# Power.net
KiCad netlist of a schematic drawn in Altium Designer
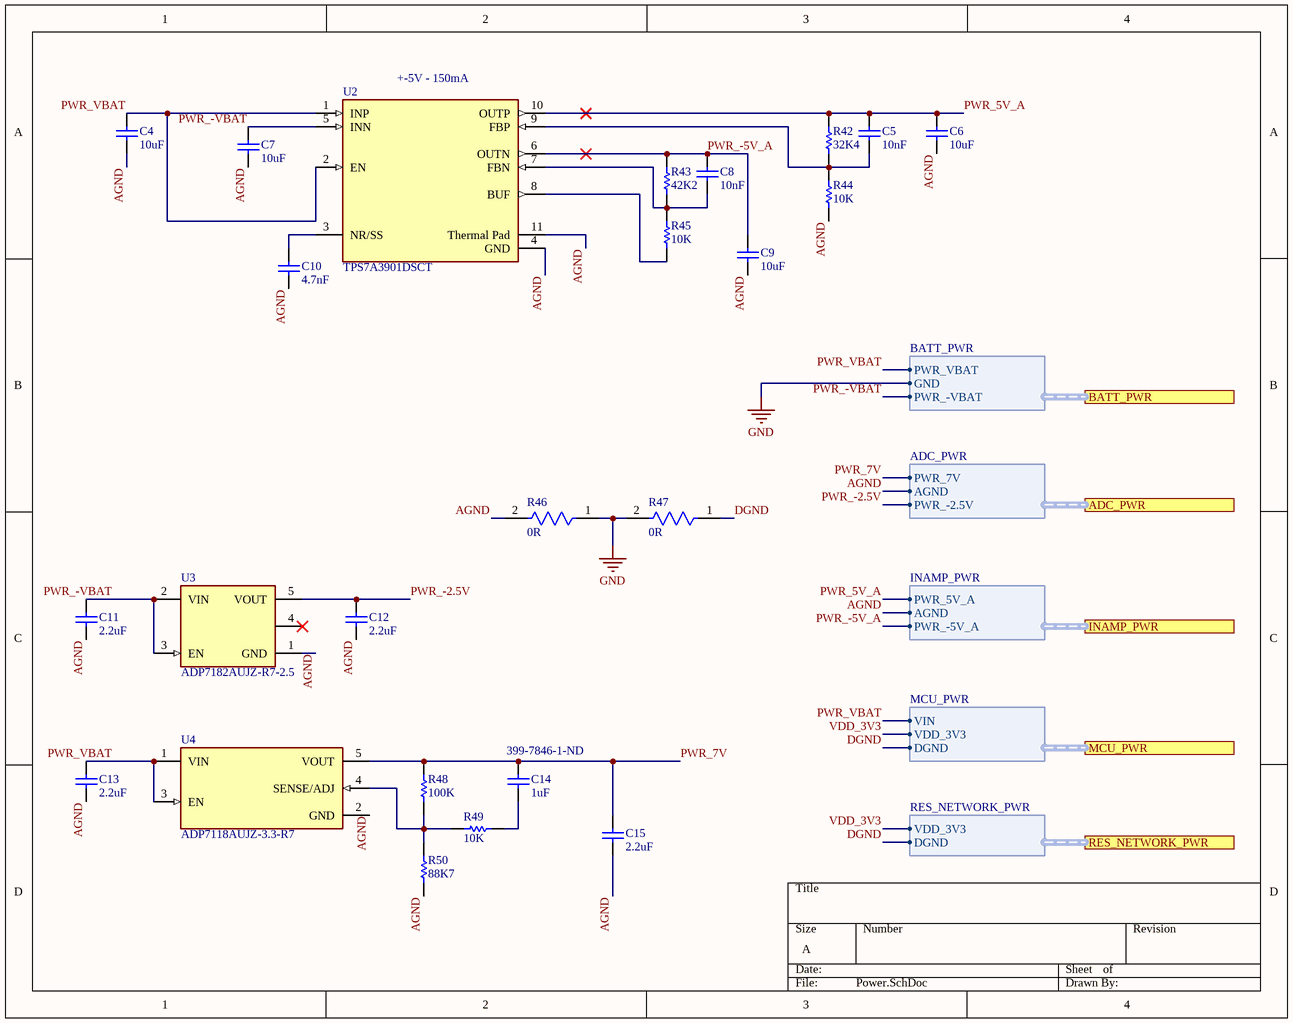
[diagram p0: Power.SchDoc]

(export (version "E")
  (design (tool "Eeschema 10.0.6"))
  (components
    (comp (ref "C4")
      (value "10uF")
      (footprint "CAPC2013X135X45ML10T25")
      (fields (field (name "PART NUMBER") "GRM21BR61E106KA73L") (field (name "MANUFACTURER") "Murata"))
      (libsource (lib "Altium Content Vault") (part "CAP"))
    )
    (comp (ref "C5")
      (value "10nF")
      (footprint "CAPC1608X90X35LL15T15")
      (fields
        (field (name "MANUFACTURER") "AVX Interconnect / Elco")
        (field (name "PART NUMBER") "06035C-103KAT2A")
      )
      (libsource (lib "Altium Content Vault") (part "CAP"))
    )
    (comp (ref "C6")
      (value "10uF")
      (footprint "CAPC2013X135X45ML10T25")
      (fields (field (name "PART NUMBER") "GRM21BR61E106KA73L") (field (name "MANUFACTURER") "Murata"))
      (libsource (lib "Altium Content Vault") (part "CAP"))
    )
    (comp (ref "C7")
      (value "10uF")
      (footprint "CAPC2013X135X45ML10T25")
      (fields (field (name "PART NUMBER") "GRM21BR61E106KA73L") (field (name "MANUFACTURER") "Murata"))
      (libsource (lib "Altium Content Vault") (part "CAP"))
    )
    (comp (ref "C8")
      (value "10nF")
      (footprint "CAPC1608X90X35LL15T15")
      (fields
        (field (name "MANUFACTURER") "AVX Interconnect / Elco")
        (field (name "PART NUMBER") "06035C-103KAT2A")
      )
      (libsource (lib "Altium Content Vault") (part "CAP"))
    )
    (comp (ref "C9")
      (value "10uF")
      (footprint "CAPC2013X135X45ML10T25")
      (fields (field (name "PART NUMBER") "GRM21BR61E106KA73L") (field (name "MANUFACTURER") "Murata"))
      (libsource (lib "Altium Content Vault") (part "CAP"))
    )
    (comp (ref "C10")
      (value "4.7nF")
      (footprint "CAPC1608X90X35LL15T15")
      (fields
        (field (name "PART NUMBER") "06035C472KAT2A")
        (field (name "MANUFACTURER") "AVX Interconnect / Elco")
      )
      (libsource (lib "Altium Content Vault") (part "CAP"))
    )
    (comp (ref "C11")
      (value "2.2uF")
      (footprint "CAPC1608X90X35ML10T15")
      (fields (field (name "PART NUMBER") "GRM188R61E225KA12D") (field (name "MANUFACTURER") "Murata"))
      (libsource (lib "Altium Content Vault") (part "CAP"))
    )
    (comp (ref "C12")
      (value "2.2uF")
      (footprint "CAPC1608X90X35ML10T15")
      (fields (field (name "PART NUMBER") "GRM188R61E225KA12D") (field (name "MANUFACTURER") "Murata"))
      (libsource (lib "Altium Content Vault") (part "CAP"))
    )
    (comp (ref "C13")
      (value "2.2uF")
      (footprint "CAPC1608X90X35ML10T15")
      (fields (field (name "PART NUMBER") "GRM188R61E225KA12D") (field (name "MANUFACTURER") "Murata"))
      (libsource (lib "Altium Content Vault") (part "CAP"))
    )
    (comp (ref "C14")
      (value "1uF")
      (footprint "CAPC1608X95X35LL15T15")
      (fields
        (field (name "MANUFACTURER") "Kemet")
        (field (name "PART NUMBER") "C0603C105K3PACTU")
        (field (name "SUPPLIER PART NUMBER 1") "399-7846-1-ND")
        (field (name "TOLERANCE") "10%")
      )
      (libsource (lib "Altium Content Vault") (part "CAP"))
    )
    (comp (ref "C15")
      (value "2.2uF")
      (footprint "CAPC1608X90X35ML10T15")
      (fields (field (name "PART NUMBER") "GRM188R61E225KA12D") (field (name "MANUFACTURER") "Murata"))
      (libsource (lib "Altium Content Vault") (part "CAP"))
    )
    (comp (ref "R42")
      (value "32K4")
      (footprint "RESC1608X55X25ML10T15")
      (fields (field (name "MANUFACTURER") "Yageo") (field (name "PART NUMBER") "RC0603FR-0732K4L"))
      (libsource (lib "Altium Content Vault") (part "RES"))
    )
    (comp (ref "R43")
      (value "42K2")
      (footprint "RESC0805(2012)_N")
      (description "42K2 0.125W 1% 0805 (2012 Metric)  SMD")
      (fields (field (name "POWER") "0.125 W") (field (name "TOLERANCE") "1 %"))
      (libsource (lib "Altium Content Vault") (part "RES"))
    )
    (comp (ref "R44")
      (value "10K")
      (footprint "RESC1609X50X30NL8T20")
      (description "Chip Resistor, 10 KOhm, +/- 1%, 100 mW, -55 to 155 degC, 0603 (1608 Metric), RoHS, Tape and Reel")
      (fields (field (name "MANUFACTURER") "Vishay Semiconductor"))
      (libsource (lib "Altium Content Vault") (part "RES-2"))
    )
    (comp (ref "R45")
      (value "10K")
      (footprint "RESC1609X50X30NL8T20")
      (description "Chip Resistor, 10 KOhm, +/- 1%, 100 mW, -55 to 155 degC, 0603 (1608 Metric), RoHS, Tape and Reel")
      (fields (field (name "MANUFACTURER") "Vishay Semiconductor"))
      (libsource (lib "Altium Content Vault") (part "RES-2"))
    )
    (comp (ref "R46")
      (value "0R")
      (footprint "FP-CR0603-MFG")
      (description "Thick Film Chip Resistors 0603 0Ω 0.1W 5%")
      (fields (field (name "TOLERANCE") "1%"))
      (libsource (lib "Altium Content Vault") (part "1029c3af85768c4190bb7ad29bc67b5"))
    )
    (comp (ref "R47")
      (value "0R")
      (footprint "FP-CR0603-MFG")
      (description "Thick Film Chip Resistors 0603 0Ω 0.1W 5%")
      (fields (field (name "TOLERANCE") "1%"))
      (libsource (lib "Altium Content Vault") (part "1029c3af85768c4190bb7ad29bc67b5"))
    )
    (comp (ref "R48")
      (value "100K")
      (footprint "RESC1608X55X25ML10T15")
      (description "Chip Resistor, 100 KOhm, +/- 1%, 0.1 W, -55 to 155 degC, 0603 (1608 Metric), RoHS, Tape and Reel")
      (fields (field (name "MANUFACTURER") "Yageo") (field (name "TOLERANCE") "1%"))
      (libsource (lib "Altium Content Vault") (part "RES-2"))
    )
    (comp (ref "R49")
      (value "10K")
      (footprint "RESC1609X50X30NL8T20")
      (description "Chip Resistor, 10 KOhm, +/- 1%, 100 mW, -55 to 155 degC, 0603 (1608 Metric), RoHS, Tape and Reel")
      (fields (field (name "MANUFACTURER") "Vishay Semiconductor"))
      (libsource (lib "Altium Content Vault") (part "RES-2"))
    )
    (comp (ref "R50")
      (value "88K7")
      (footprint "RESC1608X55X25ML10T15")
      (fields (field (name "MANUFACTURER") "Yageo") (field (name "PART NUMBER") "RC0603FR-0788K7L"))
      (libsource (lib "Altium Content Vault") (part "RES"))
    )
    (comp (ref "U2")
      (value "TPS7A3901DSCT")
      (footprint "TPS7A3901DSCT")
      (libsource (lib "SchematicLibLovro") (part "TPS7A3901DSCT"))
    )
    (comp (ref "U3")
      (value "ADP7182AUJZ-R7-2.5")
      (footprint "FP-UJ-5-IPC_A")
      (description "IC REG LIN NEG ADJ 200MA 5TSOT")
      (fields
        (field (name "MANUFACTURER") "Analog Devices")
        (field (name "MANUFACTURER PART NUMBER") "ADP7182AUJZ-R7")
      )
      (libsource (lib "Altium Content Vault") (part "92caacd0022e2ae97106797e80aebc8"))
    )
    (comp (ref "U4")
      (value "ADP7118AUJZ-3.3-R7")
      (footprint "FP-UJ-5-IPC_C")
      (description "IC REG LIN 3.3V 200MA TSOT23-5")
      (libsource (lib "Altium Content Vault") (part "5988fe09c25f52e87bcd0fa5e5a2534"))
    )
  )
  (nets
    (net (code "6") (name "/AGND") (class "Default")
      (node (ref "C10") (pin "1") (pinfunction "1_1") (pintype "passive"))
      (node (ref "C11") (pin "1") (pinfunction "1_1") (pintype "passive"))
      (node (ref "C12") (pin "1") (pinfunction "1_1") (pintype "passive"))
      (node (ref "C13") (pin "1") (pinfunction "1_1") (pintype "passive"))
      (node (ref "C15") (pin "1") (pinfunction "1_1") (pintype "passive"))
      (node (ref "C4") (pin "1") (pinfunction "1_1") (pintype "passive"))
      (node (ref "C6") (pin "1") (pinfunction "1_1") (pintype "passive"))
      (node (ref "C7") (pin "1") (pinfunction "1_1") (pintype "passive"))
      (node (ref "C9") (pin "1") (pinfunction "1_1") (pintype "passive"))
      (node (ref "R44") (pin "1") (pinfunction "1_1") (pintype "passive"))
      (node (ref "R46") (pin "2") (pinfunction "2_2") (pintype "passive"))
      (node (ref "R50") (pin "1") (pinfunction "1_1") (pintype "passive"))
      (node (ref "U2") (pin "11") (pinfunction "Thermal_Pad_11") (pintype "passive"))
      (node (ref "U2") (pin "4") (pinfunction "GND_4") (pintype "power_in"))
      (node (ref "U3") (pin "1") (pinfunction "GND_1") (pintype "power_in"))
      (node (ref "U4") (pin "2") (pinfunction "GND_2") (pintype "power_in"))
    )
    (net (code "7") (name "/DGND") (class "Default")
      (node (ref "R47") (pin "1") (pinfunction "1_1") (pintype "passive"))
    )
    (net (code "8") (name "/PWR_-2.5V") (class "Default")
      (node (ref "C12") (pin "2") (pinfunction "2_2") (pintype "passive"))
      (node (ref "U3") (pin "5") (pinfunction "VOUT_5") (pintype "power_in"))
    )
    (net (code "9") (name "/PWR_-5V_A") (class "Default")
      (node (ref "C8") (pin "2") (pinfunction "2_2") (pintype "passive"))
      (node (ref "C9") (pin "2") (pinfunction "2_2") (pintype "passive"))
      (node (ref "R43") (pin "2") (pinfunction "2_2") (pintype "passive"))
      (node (ref "U2") (pin "6") (pinfunction "OUTN_6") (pintype "output"))
    )
    (net (code "10") (name "/PWR_-VBAT") (class "Default")
      (node (ref "C11") (pin "2") (pinfunction "2_2") (pintype "passive"))
      (node (ref "C7") (pin "2") (pinfunction "2_2") (pintype "passive"))
      (node (ref "U2") (pin "5") (pinfunction "INN_5") (pintype "input"))
      (node (ref "U3") (pin "2") (pinfunction "VIN_2") (pintype "power_in"))
      (node (ref "U3") (pin "3") (pinfunction "EN_3") (pintype "input"))
    )
    (net (code "11") (name "/PWR_5V_A") (class "Default")
      (node (ref "C5") (pin "2") (pinfunction "2_2") (pintype "passive"))
      (node (ref "C6") (pin "2") (pinfunction "2_2") (pintype "passive"))
      (node (ref "R42") (pin "1") (pinfunction "1_1") (pintype "passive"))
      (node (ref "U2") (pin "10") (pinfunction "OUTP_10") (pintype "output"))
    )
    (net (code "12") (name "/PWR_7V") (class "Default")
      (node (ref "C14") (pin "2") (pinfunction "2_2") (pintype "passive"))
      (node (ref "C15") (pin "2") (pinfunction "2_2") (pintype "passive"))
      (node (ref "R48") (pin "2") (pinfunction "2_2") (pintype "passive"))
      (node (ref "U4") (pin "5") (pinfunction "VOUT_5") (pintype "passive"))
    )
    (net (code "13") (name "/PWR_VBAT") (class "Default")
      (node (ref "C13") (pin "2") (pinfunction "2_2") (pintype "passive"))
      (node (ref "C4") (pin "2") (pinfunction "2_2") (pintype "passive"))
      (node (ref "U2") (pin "1") (pinfunction "INP_1") (pintype "input"))
      (node (ref "U2") (pin "2") (pinfunction "EN_2") (pintype "input"))
      (node (ref "U4") (pin "1") (pinfunction "VIN_1") (pintype "power_in"))
      (node (ref "U4") (pin "3") (pinfunction "EN_3") (pintype "input"))
    )
    (net (code "20") (name "GND") (class "Default")
      (node (ref "R46") (pin "1") (pinfunction "1_1") (pintype "passive"))
      (node (ref "R47") (pin "2") (pinfunction "2_2") (pintype "passive"))
    )
    (net (code "21") (name "Net-(C14-Pad1)") (class "Default")
      (node (ref "C14") (pin "1") (pinfunction "1_1") (pintype "passive"))
      (node (ref "R49") (pin "2") (pinfunction "2_2") (pintype "passive"))
    )
    (net (code "22") (name "Net-(U2-BUF)") (class "Default")
      (node (ref "R45") (pin "1") (pinfunction "1_1") (pintype "passive"))
      (node (ref "U2") (pin "8") (pinfunction "BUF_8") (pintype "output"))
    )
    (net (code "23") (name "Net-(U2-FBN)") (class "Default")
      (node (ref "C8") (pin "1") (pinfunction "1_1") (pintype "passive"))
      (node (ref "R43") (pin "1") (pinfunction "1_1") (pintype "passive"))
      (node (ref "R45") (pin "2") (pinfunction "2_2") (pintype "passive"))
      (node (ref "U2") (pin "7") (pinfunction "FBN_7") (pintype "input"))
    )
    (net (code "24") (name "Net-(U2-FBP)") (class "Default")
      (node (ref "C5") (pin "1") (pinfunction "1_1") (pintype "passive"))
      (node (ref "R42") (pin "2") (pinfunction "2_2") (pintype "passive"))
      (node (ref "R44") (pin "2") (pinfunction "2_2") (pintype "passive"))
      (node (ref "U2") (pin "9") (pinfunction "FBP_9") (pintype "input"))
    )
    (net (code "25") (name "Net-(U2-NR{slash}SS)") (class "Default")
      (node (ref "C10") (pin "2") (pinfunction "2_2") (pintype "passive"))
      (node (ref "U2") (pin "3") (pinfunction "NR/SS_3") (pintype "passive"))
    )
    (net (code "26") (name "Net-(U4-SENSE{slash}ADJ)") (class "Default")
      (node (ref "R48") (pin "1") (pinfunction "1_1") (pintype "passive"))
      (node (ref "R49") (pin "1") (pinfunction "1_1") (pintype "passive"))
      (node (ref "R50") (pin "2") (pinfunction "2_2") (pintype "passive"))
      (node (ref "U4") (pin "4") (pinfunction "SENSE/ADJ_4") (pintype "input"))
    )
    (net (code "27") (name "unconnected-(U3-ADJ-Pad4)") (class "Default")
      (node (ref "U3") (pin "4") (pinfunction "ADJ_4") (pintype "passive+no_connect"))
    )
  )
)
